# 130806_AriloRX_FINAL_PCB1.net
KiCad netlist of a schematic drawn in EAGLE
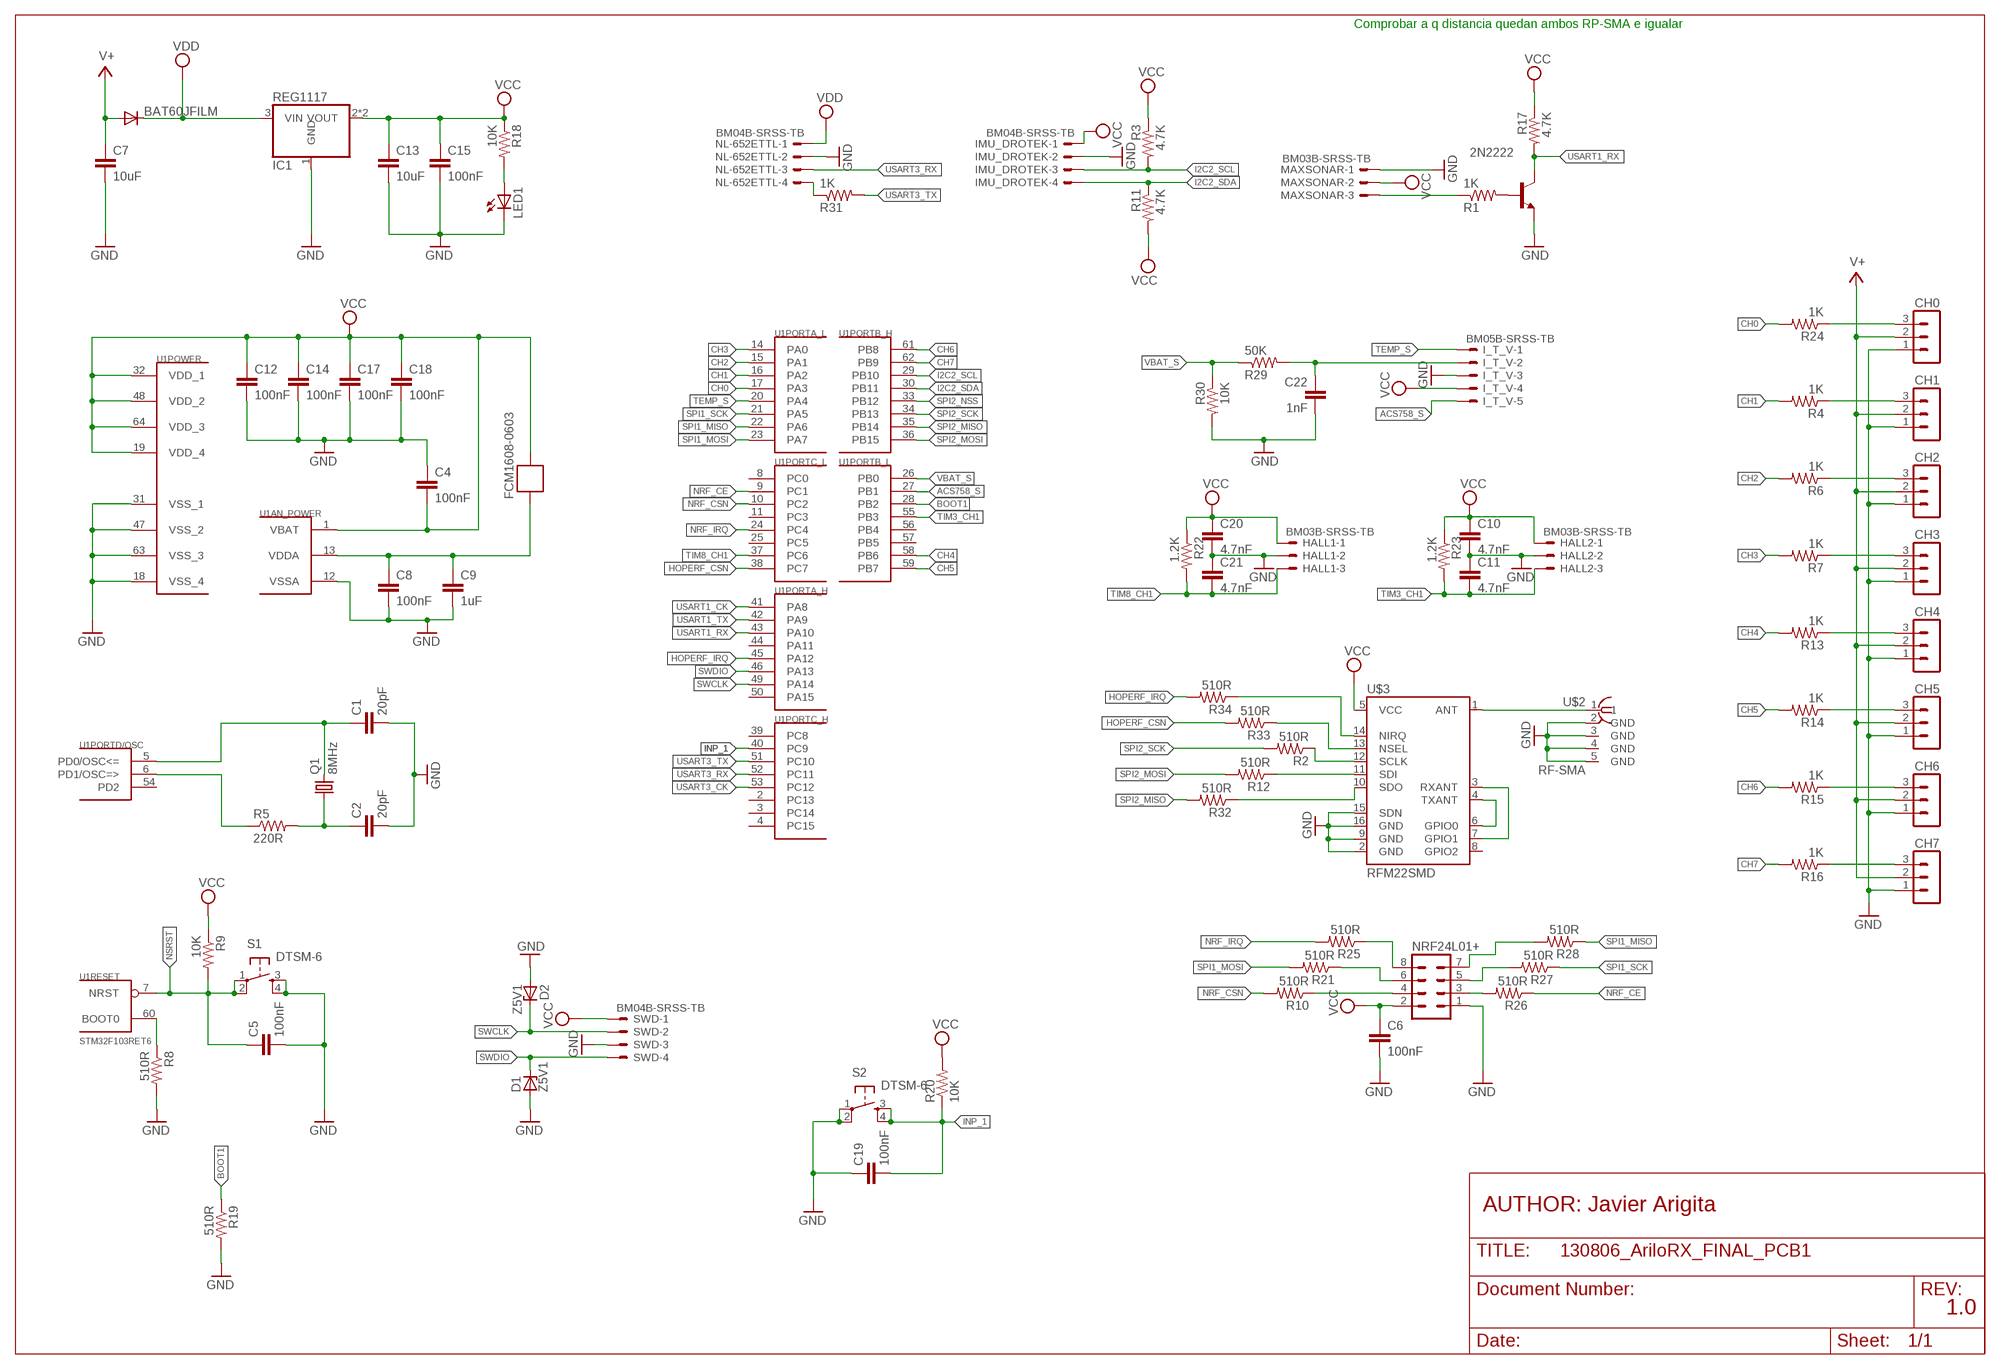
[diagram p0: schematic, sheet 1]

(export (version "E")
  (design (tool "Eeschema 10.0.6"))
  (components
    (comp (ref "2N2222")
      (value "MMBT2222ALT1-NPN-SOT23-BEC")
      (footprint "eagle-import:SOT23-BEC")
      (libsource (lib "eagle-import") (part "-NPN-SOT23-BECMMBT2222ALT1"))
    )
    (comp (ref "BAT60JFILM")
      (value "DIODE-SOD323-R")
      (footprint "eagle-import:SOD323-R")
      (libsource (lib "eagle-import") (part "DIODE-SOD323-R"))
    )
    (comp (ref "C1")
      (value "20pF")
      (footprint "eagle-import:C0805")
      (libsource (lib "eagle-import") (part "C-EUC0805"))
    )
    (comp (ref "C2")
      (value "20pF")
      (footprint "eagle-import:C0805")
      (libsource (lib "eagle-import") (part "C-EUC0805"))
    )
    (comp (ref "C4")
      (value "100nF")
      (footprint "eagle-import:C0805")
      (libsource (lib "eagle-import") (part "C-EUC0805"))
    )
    (comp (ref "C5")
      (value "100nF")
      (footprint "eagle-import:C0805")
      (libsource (lib "eagle-import") (part "C-EUC0805"))
    )
    (comp (ref "C6")
      (value "100nF")
      (footprint "eagle-import:C0805")
      (libsource (lib "eagle-import") (part "C-EUC0805"))
    )
    (comp (ref "C7")
      (value "10uF")
      (footprint "eagle-import:C3216")
      (libsource (lib "eagle-import") (part "resistor_C-EUC3216"))
    )
    (comp (ref "C8")
      (value "100nF")
      (footprint "eagle-import:C0805")
      (libsource (lib "eagle-import") (part "C-EUC0805"))
    )
    (comp (ref "C9")
      (value "1uF")
      (footprint "eagle-import:C3216")
      (libsource (lib "eagle-import") (part "resistor_C-EUC3216"))
    )
    (comp (ref "C10")
      (value "4.7nF")
      (footprint "eagle-import:C0805")
      (libsource (lib "eagle-import") (part "C-EUC0805"))
    )
    (comp (ref "C11")
      (value "4.7nF")
      (footprint "eagle-import:C0805")
      (libsource (lib "eagle-import") (part "C-EUC0805"))
    )
    (comp (ref "C12")
      (value "100nF")
      (footprint "eagle-import:C0805")
      (libsource (lib "eagle-import") (part "C-EUC0805"))
    )
    (comp (ref "C13")
      (value "10uF")
      (footprint "eagle-import:C3216")
      (libsource (lib "eagle-import") (part "resistor_C-EUC3216"))
    )
    (comp (ref "C14")
      (value "100nF")
      (footprint "eagle-import:C0805")
      (libsource (lib "eagle-import") (part "C-EUC0805"))
    )
    (comp (ref "C15")
      (value "100nF")
      (footprint "eagle-import:C0805")
      (libsource (lib "eagle-import") (part "C-EUC0805"))
    )
    (comp (ref "C17")
      (value "100nF")
      (footprint "eagle-import:C0805")
      (libsource (lib "eagle-import") (part "C-EUC0805"))
    )
    (comp (ref "C18")
      (value "100nF")
      (footprint "eagle-import:C0805")
      (libsource (lib "eagle-import") (part "C-EUC0805"))
    )
    (comp (ref "C19")
      (value "100nF")
      (footprint "eagle-import:C0805")
      (libsource (lib "eagle-import") (part "C-EUC0805"))
    )
    (comp (ref "C20")
      (value "4.7nF")
      (footprint "eagle-import:C0805")
      (libsource (lib "eagle-import") (part "C-EUC0805"))
    )
    (comp (ref "C21")
      (value "4.7nF")
      (footprint "eagle-import:C0805")
      (libsource (lib "eagle-import") (part "C-EUC0805"))
    )
    (comp (ref "C22")
      (value "1nF")
      (footprint "eagle-import:C0805")
      (libsource (lib "eagle-import") (part "C-EUC0805"))
    )
    (comp (ref "CH0")
      (value "MA03-1")
      (footprint "eagle-import:MA03-1")
      (libsource (lib "eagle-import") (part "MA03-1"))
    )
    (comp (ref "CH1")
      (value "MA03-1")
      (footprint "eagle-import:MA03-1")
      (libsource (lib "eagle-import") (part "MA03-1"))
    )
    (comp (ref "CH2")
      (value "MA03-1")
      (footprint "eagle-import:MA03-1")
      (libsource (lib "eagle-import") (part "MA03-1"))
    )
    (comp (ref "CH3")
      (value "MA03-1")
      (footprint "eagle-import:MA03-1")
      (libsource (lib "eagle-import") (part "MA03-1"))
    )
    (comp (ref "CH4")
      (value "MA03-1")
      (footprint "eagle-import:MA03-1")
      (libsource (lib "eagle-import") (part "MA03-1"))
    )
    (comp (ref "CH5")
      (value "MA03-1")
      (footprint "eagle-import:MA03-1")
      (libsource (lib "eagle-import") (part "MA03-1"))
    )
    (comp (ref "CH6")
      (value "MA03-1")
      (footprint "eagle-import:MA03-1")
      (libsource (lib "eagle-import") (part "MA03-1"))
    )
    (comp (ref "CH7")
      (value "MA03-1")
      (footprint "eagle-import:MA03-1")
      (libsource (lib "eagle-import") (part "MA03-1"))
    )
    (comp (ref "D1")
      (value "Z5V1")
      (footprint "eagle-import:SOD80C")
      (libsource (lib "eagle-import") (part "ZENER-DIODESOD80C"))
    )
    (comp (ref "D2")
      (value "Z5V1")
      (footprint "eagle-import:SOD80C")
      (libsource (lib "eagle-import") (part "ZENER-DIODESOD80C"))
    )
    (comp (ref "FCM1608-0603")
      (value "FERRITE-BEAD")
      (footprint "eagle-import:R0603")
      (libsource (lib "eagle-import") (part "FERRITE-BEAD"))
    )
    (comp (ref "HALL1")
      (value "BM03B-SRSS-TB")
      (footprint "eagle-import:BM03B-SRSS-TB")
      (libsource (lib "eagle-import") (part "?M03B-SRSS-TBB"))
    )
    (comp (ref "HALL2")
      (value "BM03B-SRSS-TB")
      (footprint "eagle-import:BM03B-SRSS-TB")
      (libsource (lib "eagle-import") (part "?M03B-SRSS-TBB"))
    )
    (comp (ref "IC1")
      (value "REG1117")
      (footprint "eagle-import:SOT223")
      (libsource (lib "eagle-import") (part "REG1117"))
    )
    (comp (ref "IMU_DROTEK")
      (value "BM04B-SRSS-TB")
      (footprint "eagle-import:BM04B-SRSS-TB")
      (libsource (lib "eagle-import") (part "?M04B-SRSS-TBB"))
    )
    (comp (ref "I_T_V")
      (value "BM05B-SRSS-TB")
      (footprint "eagle-import:BM05B-SRSS-TB")
      (libsource (lib "eagle-import") (part "?M05B-SRSS-TBB"))
    )
    (comp (ref "LED1")
      (value "LED0805")
      (footprint "eagle-import:CHIPLED_0805")
      (libsource (lib "eagle-import") (part "LED0805"))
    )
    (comp (ref "MAXSONAR")
      (value "BM03B-SRSS-TB")
      (footprint "eagle-import:BM03B-SRSS-TB")
      (libsource (lib "eagle-import") (part "?M03B-SRSS-TBB"))
    )
    (comp (ref "NL-652ETTL")
      (value "BM04B-SRSS-TB")
      (footprint "eagle-import:BM04B-SRSS-TB")
      (libsource (lib "eagle-import") (part "?M04B-SRSS-TBB"))
    )
    (comp (ref "NRF24L01+")
      (value "MA04-2")
      (footprint "eagle-import:MA04-2")
      (libsource (lib "eagle-import") (part "MA04-2"))
    )
    (comp (ref "Q1")
      (value "8MHz")
      (footprint "eagle-import:SM49")
      (libsource (lib "eagle-import") (part "CRYSTALSM49"))
    )
    (comp (ref "R1")
      (value "1K")
      (footprint "eagle-import:R0805")
      (libsource (lib "eagle-import") (part "RESISTOR0805"))
    )
    (comp (ref "R2")
      (value "510R")
      (footprint "eagle-import:R0805")
      (libsource (lib "eagle-import") (part "RESISTOR0805"))
    )
    (comp (ref "R3")
      (value "4.7K")
      (footprint "eagle-import:R0805")
      (libsource (lib "eagle-import") (part "RESISTOR0805"))
    )
    (comp (ref "R4")
      (value "1K")
      (footprint "eagle-import:R0805")
      (libsource (lib "eagle-import") (part "RESISTOR0805"))
    )
    (comp (ref "R5")
      (value "220R")
      (footprint "eagle-import:R0805")
      (libsource (lib "eagle-import") (part "RESISTOR0805"))
    )
    (comp (ref "R6")
      (value "1K")
      (footprint "eagle-import:R0805")
      (libsource (lib "eagle-import") (part "RESISTOR0805"))
    )
    (comp (ref "R7")
      (value "1K")
      (footprint "eagle-import:R0805")
      (libsource (lib "eagle-import") (part "RESISTOR0805"))
    )
    (comp (ref "R8")
      (value "510R")
      (footprint "eagle-import:R0805")
      (libsource (lib "eagle-import") (part "RESISTOR0805"))
    )
    (comp (ref "R9")
      (value "10K")
      (footprint "eagle-import:R0805")
      (libsource (lib "eagle-import") (part "RESISTOR0805"))
    )
    (comp (ref "R10")
      (value "510R")
      (footprint "eagle-import:R0805")
      (libsource (lib "eagle-import") (part "RESISTOR0805"))
    )
    (comp (ref "R11")
      (value "4.7K")
      (footprint "eagle-import:R0805")
      (libsource (lib "eagle-import") (part "RESISTOR0805"))
    )
    (comp (ref "R12")
      (value "510R")
      (footprint "eagle-import:R0805")
      (libsource (lib "eagle-import") (part "RESISTOR0805"))
    )
    (comp (ref "R13")
      (value "1K")
      (footprint "eagle-import:R0805")
      (libsource (lib "eagle-import") (part "RESISTOR0805"))
    )
    (comp (ref "R14")
      (value "1K")
      (footprint "eagle-import:R0805")
      (libsource (lib "eagle-import") (part "RESISTOR0805"))
    )
    (comp (ref "R15")
      (value "1K")
      (footprint "eagle-import:R0805")
      (libsource (lib "eagle-import") (part "RESISTOR0805"))
    )
    (comp (ref "R16")
      (value "1K")
      (footprint "eagle-import:R0805")
      (libsource (lib "eagle-import") (part "RESISTOR0805"))
    )
    (comp (ref "R17")
      (value "4.7K")
      (footprint "eagle-import:R0805")
      (libsource (lib "eagle-import") (part "RESISTOR0805"))
    )
    (comp (ref "R18")
      (value "10K")
      (footprint "eagle-import:R0805")
      (libsource (lib "eagle-import") (part "RESISTOR0805"))
    )
    (comp (ref "R19")
      (value "510R")
      (footprint "eagle-import:R0805")
      (libsource (lib "eagle-import") (part "RESISTOR0805"))
    )
    (comp (ref "R20")
      (value "10K")
      (footprint "eagle-import:R0805")
      (libsource (lib "eagle-import") (part "RESISTOR0805"))
    )
    (comp (ref "R21")
      (value "510R")
      (footprint "eagle-import:R0805")
      (libsource (lib "eagle-import") (part "RESISTOR0805"))
    )
    (comp (ref "R22")
      (value "1.2K")
      (footprint "eagle-import:R0805")
      (libsource (lib "eagle-import") (part "RESISTOR0805"))
    )
    (comp (ref "R23")
      (value "1.2K")
      (footprint "eagle-import:R0805")
      (libsource (lib "eagle-import") (part "RESISTOR0805"))
    )
    (comp (ref "R24")
      (value "1K")
      (footprint "eagle-import:R0805")
      (libsource (lib "eagle-import") (part "RESISTOR0805"))
    )
    (comp (ref "R25")
      (value "510R")
      (footprint "eagle-import:R0805")
      (libsource (lib "eagle-import") (part "RESISTOR0805"))
    )
    (comp (ref "R26")
      (value "510R")
      (footprint "eagle-import:R0805")
      (libsource (lib "eagle-import") (part "RESISTOR0805"))
    )
    (comp (ref "R27")
      (value "510R")
      (footprint "eagle-import:R0805")
      (libsource (lib "eagle-import") (part "RESISTOR0805"))
    )
    (comp (ref "R28")
      (value "510R")
      (footprint "eagle-import:R0805")
      (libsource (lib "eagle-import") (part "RESISTOR0805"))
    )
    (comp (ref "R29")
      (value "50K")
      (footprint "eagle-import:R0805")
      (libsource (lib "eagle-import") (part "RESISTOR0805"))
    )
    (comp (ref "R30")
      (value "10K")
      (footprint "eagle-import:R0805")
      (libsource (lib "eagle-import") (part "RESISTOR0805"))
    )
    (comp (ref "R31")
      (value "1K")
      (footprint "eagle-import:R0805")
      (libsource (lib "eagle-import") (part "RESISTOR0805"))
    )
    (comp (ref "R32")
      (value "510R")
      (footprint "eagle-import:R0805")
      (libsource (lib "eagle-import") (part "RESISTOR0805"))
    )
    (comp (ref "R33")
      (value "510R")
      (footprint "eagle-import:R0805")
      (libsource (lib "eagle-import") (part "RESISTOR0805"))
    )
    (comp (ref "R34")
      (value "510R")
      (footprint "eagle-import:R0805")
      (libsource (lib "eagle-import") (part "RESISTOR0805"))
    )
    (comp (ref "S1")
      (value "DTSM-6")
      (footprint "eagle-import:DTSM-6")
      (libsource (lib "eagle-import") (part "DTSM-6"))
    )
    (comp (ref "S2")
      (value "DTSM-6")
      (footprint "eagle-import:DTSM-6")
      (libsource (lib "eagle-import") (part "DTSM-6"))
    )
    (comp (ref "SWD")
      (value "BM04B-SRSS-TB")
      (footprint "eagle-import:BM04B-SRSS-TB")
      (libsource (lib "eagle-import") (part "?M04B-SRSS-TBB"))
    )
    (comp (ref "U$2")
      (value "RF-SMA")
      (footprint "eagle-import:BU-SMA-H")
      (libsource (lib "eagle-import") (part "RF-SMA"))
    )
    (comp (ref "U$3")
      (value "RFM22SMD")
      (footprint "eagle-import:RFM22-XXX-S2")
      (libsource (lib "eagle-import") (part "RFM22SMD"))
    )
    (comp (ref "U1")
      (value "STM32F103RET6")
      (footprint "eagle-import:TQFP64")
      (libsource (lib "eagle-import") (part "STM32F10XRXT6"))
    )
  )
  (nets
    (net (code "1") (name "ACS758_S") (class "Default")
      (node (ref "I_T_V") (pin "5") (pinfunction "S_5") (pintype "passive"))
      (node (ref "U1") (pin "27") (pinfunction "PB1_27") (pintype "bidirectional"))
    )
    (net (code "2") (name "BOOT1") (class "Default")
      (node (ref "R19") (pin "1") (pinfunction "1_1") (pintype "passive"))
      (node (ref "U1") (pin "28") (pinfunction "PB2_28") (pintype "bidirectional"))
    )
    (net (code "3") (name "CH0") (class "Default")
      (node (ref "R24") (pin "2") (pinfunction "2_2") (pintype "passive"))
      (node (ref "U1") (pin "17") (pinfunction "PA3_17") (pintype "bidirectional"))
    )
    (net (code "4") (name "CH1") (class "Default")
      (node (ref "R4") (pin "2") (pinfunction "2_2") (pintype "passive"))
      (node (ref "U1") (pin "16") (pinfunction "PA2_16") (pintype "bidirectional"))
    )
    (net (code "5") (name "CH2") (class "Default")
      (node (ref "R6") (pin "2") (pinfunction "2_2") (pintype "passive"))
      (node (ref "U1") (pin "15") (pinfunction "PA1_15") (pintype "bidirectional"))
    )
    (net (code "6") (name "CH3") (class "Default")
      (node (ref "R7") (pin "2") (pinfunction "2_2") (pintype "passive"))
      (node (ref "U1") (pin "14") (pinfunction "PA0_14") (pintype "bidirectional"))
    )
    (net (code "7") (name "CH4") (class "Default")
      (node (ref "R13") (pin "2") (pinfunction "2_2") (pintype "passive"))
      (node (ref "U1") (pin "58") (pinfunction "PB6_58") (pintype "bidirectional"))
    )
    (net (code "8") (name "CH5") (class "Default")
      (node (ref "R14") (pin "2") (pinfunction "2_2") (pintype "passive"))
      (node (ref "U1") (pin "59") (pinfunction "PB7_59") (pintype "bidirectional"))
    )
    (net (code "9") (name "CH6") (class "Default")
      (node (ref "R15") (pin "2") (pinfunction "2_2") (pintype "passive"))
      (node (ref "U1") (pin "61") (pinfunction "PB8_61") (pintype "bidirectional"))
    )
    (net (code "10") (name "CH7") (class "Default")
      (node (ref "R16") (pin "2") (pinfunction "2_2") (pintype "passive"))
      (node (ref "U1") (pin "62") (pinfunction "PB9_62") (pintype "bidirectional"))
    )
    (net (code "11") (name "GND") (class "Default")
      (node (ref "2N2222") (pin "E") (pinfunction "E_E") (pintype "passive"))
      (node (ref "C1") (pin "2") (pinfunction "2_2") (pintype "passive"))
      (node (ref "C10") (pin "2") (pinfunction "2_2") (pintype "passive"))
      (node (ref "C11") (pin "1") (pinfunction "1_1") (pintype "passive"))
      (node (ref "C12") (pin "2") (pinfunction "2_2") (pintype "passive"))
      (node (ref "C13") (pin "2") (pinfunction "2_2") (pintype "passive"))
      (node (ref "C14") (pin "2") (pinfunction "2_2") (pintype "passive"))
      (node (ref "C15") (pin "2") (pinfunction "2_2") (pintype "passive"))
      (node (ref "C17") (pin "2") (pinfunction "2_2") (pintype "passive"))
      (node (ref "C18") (pin "2") (pinfunction "2_2") (pintype "passive"))
      (node (ref "C19") (pin "1") (pinfunction "1_1") (pintype "passive"))
      (node (ref "C2") (pin "2") (pinfunction "2_2") (pintype "passive"))
      (node (ref "C20") (pin "2") (pinfunction "2_2") (pintype "passive"))
      (node (ref "C21") (pin "1") (pinfunction "1_1") (pintype "passive"))
      (node (ref "C22") (pin "2") (pinfunction "2_2") (pintype "passive"))
      (node (ref "C4") (pin "1") (pinfunction "1_1") (pintype "passive"))
      (node (ref "C5") (pin "2") (pinfunction "2_2") (pintype "passive"))
      (node (ref "C6") (pin "2") (pinfunction "2_2") (pintype "passive"))
      (node (ref "C7") (pin "2") (pinfunction "2_2") (pintype "passive"))
      (node (ref "C8") (pin "2") (pinfunction "2_2") (pintype "passive"))
      (node (ref "C9") (pin "2") (pinfunction "2_2") (pintype "passive"))
      (node (ref "CH0") (pin "1") (pinfunction "1_1") (pintype "passive"))
      (node (ref "CH1") (pin "1") (pinfunction "1_1") (pintype "passive"))
      (node (ref "CH2") (pin "1") (pinfunction "1_1") (pintype "passive"))
      (node (ref "CH3") (pin "1") (pinfunction "1_1") (pintype "passive"))
      (node (ref "CH4") (pin "1") (pinfunction "1_1") (pintype "passive"))
      (node (ref "CH5") (pin "1") (pinfunction "1_1") (pintype "passive"))
      (node (ref "CH6") (pin "1") (pinfunction "1_1") (pintype "passive"))
      (node (ref "CH7") (pin "1") (pinfunction "1_1") (pintype "passive"))
      (node (ref "D1") (pin "A") (pinfunction "A_A") (pintype "passive"))
      (node (ref "D2") (pin "A") (pinfunction "A_A") (pintype "passive"))
      (node (ref "HALL1") (pin "2") (pinfunction "S_2") (pintype "passive"))
      (node (ref "HALL2") (pin "2") (pinfunction "S_2") (pintype "passive"))
      (node (ref "IC1") (pin "1") (pinfunction "GND_1") (pintype "power_in"))
      (node (ref "IMU_DROTEK") (pin "2") (pinfunction "S_2") (pintype "passive"))
      (node (ref "I_T_V") (pin "3") (pinfunction "S_3") (pintype "passive"))
      (node (ref "LED1") (pin "C") (pinfunction "C_C") (pintype "passive"))
      (node (ref "MAXSONAR") (pin "1") (pinfunction "S_1") (pintype "passive"))
      (node (ref "NL-652ETTL") (pin "2") (pinfunction "S_2") (pintype "passive"))
      (node (ref "NRF24L01+") (pin "1") (pinfunction "1_1") (pintype "passive"))
      (node (ref "R19") (pin "2") (pinfunction "2_2") (pintype "passive"))
      (node (ref "R30") (pin "2") (pinfunction "2_2") (pintype "passive"))
      (node (ref "R8") (pin "2") (pinfunction "2_2") (pintype "passive"))
      (node (ref "S1") (pin "3") (pinfunction "3_3") (pintype "passive"))
      (node (ref "S1") (pin "4") (pinfunction "4_4") (pintype "passive"))
      (node (ref "S2") (pin "1") (pinfunction "1_1") (pintype "passive"))
      (node (ref "S2") (pin "2") (pinfunction "2_2") (pintype "passive"))
      (node (ref "SWD") (pin "3") (pinfunction "S_3") (pintype "passive"))
      (node (ref "U$2") (pin "2") (pinfunction "GND_2") (pintype "power_in"))
      (node (ref "U$2") (pin "3") (pinfunction "GND_3") (pintype "bidirectional"))
      (node (ref "U$2") (pin "4") (pinfunction "GND_4") (pintype "bidirectional"))
      (node (ref "U$2") (pin "5") (pinfunction "GND_5") (pintype "bidirectional"))
      (node (ref "U$3") (pin "15") (pinfunction "SDN_15") (pintype "input"))
      (node (ref "U$3") (pin "16") (pinfunction "GND_16") (pintype "power_in"))
      (node (ref "U$3") (pin "2") (pinfunction "GND_2") (pintype "power_in"))
      (node (ref "U$3") (pin "9") (pinfunction "GND_9") (pintype "power_in"))
      (node (ref "U1") (pin "12") (pinfunction "VSSA_12") (pintype "power_in"))
      (node (ref "U1") (pin "18") (pinfunction "VSS_4_18") (pintype "power_in"))
      (node (ref "U1") (pin "31") (pinfunction "VSS_1_31") (pintype "power_in"))
      (node (ref "U1") (pin "47") (pinfunction "VSS_2_47") (pintype "power_in"))
      (node (ref "U1") (pin "63") (pinfunction "VSS_3_63") (pintype "power_in"))
    )
    (net (code "12") (name "HOPERF_CSN") (class "Default")
      (node (ref "R33") (pin "2") (pinfunction "2_2") (pintype "passive"))
      (node (ref "U1") (pin "38") (pinfunction "PC7_38") (pintype "bidirectional"))
    )
    (net (code "13") (name "HOPERF_IRQ") (class "Default")
      (node (ref "R34") (pin "2") (pinfunction "2_2") (pintype "passive"))
      (node (ref "U1") (pin "45") (pinfunction "PA12_45") (pintype "bidirectional"))
    )
    (net (code "14") (name "I2C2_SCL") (class "Default")
      (node (ref "IMU_DROTEK") (pin "3") (pinfunction "S_3") (pintype "passive"))
      (node (ref "R3") (pin "2") (pinfunction "2_2") (pintype "passive"))
      (node (ref "U1") (pin "29") (pinfunction "PB10_29") (pintype "bidirectional"))
    )
    (net (code "15") (name "I2C2_SDA") (class "Default")
      (node (ref "IMU_DROTEK") (pin "4") (pinfunction "S_4") (pintype "passive"))
      (node (ref "R11") (pin "1") (pinfunction "1_1") (pintype "passive"))
      (node (ref "U1") (pin "30") (pinfunction "PB11_30") (pintype "bidirectional"))
    )
    (net (code "16") (name "INP_1") (class "Default")
      (node (ref "C19") (pin "2") (pinfunction "2_2") (pintype "passive"))
      (node (ref "R20") (pin "1") (pinfunction "1_1") (pintype "passive"))
      (node (ref "S2") (pin "3") (pinfunction "3_3") (pintype "passive"))
      (node (ref "S2") (pin "4") (pinfunction "4_4") (pintype "passive"))
      (node (ref "U1") (pin "40") (pinfunction "PC9_40") (pintype "bidirectional"))
    )
    (net (code "17") (name "NRF_CE") (class "Default")
      (node (ref "R26") (pin "1") (pinfunction "1_1") (pintype "passive"))
      (node (ref "U1") (pin "9") (pinfunction "PC1_9") (pintype "bidirectional"))
    )
    (net (code "18") (name "NRF_CSN") (class "Default")
      (node (ref "R10") (pin "2") (pinfunction "2_2") (pintype "passive"))
      (node (ref "U1") (pin "10") (pinfunction "PC2_10") (pintype "bidirectional"))
    )
    (net (code "19") (name "NRF_IRQ") (class "Default")
      (node (ref "R25") (pin "2") (pinfunction "2_2") (pintype "passive"))
      (node (ref "U1") (pin "24") (pinfunction "PC4_24") (pintype "bidirectional"))
    )
    (net (code "20") (name "NSRST") (class "Default")
      (node (ref "C5") (pin "1") (pinfunction "1_1") (pintype "passive"))
      (node (ref "R9") (pin "2") (pinfunction "2_2") (pintype "passive"))
      (node (ref "S1") (pin "1") (pinfunction "1_1") (pintype "passive"))
      (node (ref "S1") (pin "2") (pinfunction "2_2") (pintype "passive"))
      (node (ref "U1") (pin "7") (pinfunction "NRST_7") (pintype "input"))
    )
    (net (code "21") (name "Net-(2N2222-PadB)") (class "Default")
      (node (ref "2N2222") (pin "B") (pinfunction "B_B") (pintype "passive"))
      (node (ref "R1") (pin "2") (pinfunction "2_2") (pintype "passive"))
    )
    (net (code "22") (name "Net-(C2-Pad1)") (class "Default")
      (node (ref "C2") (pin "1") (pinfunction "1_1") (pintype "passive"))
      (node (ref "Q1") (pin "1") (pinfunction "1_1") (pintype "passive"))
      (node (ref "R5") (pin "2") (pinfunction "2_2") (pintype "passive"))
    )
    (net (code "23") (name "Net-(CH0-Pad3)") (class "Default")
      (node (ref "CH0") (pin "3") (pinfunction "3_3") (pintype "passive"))
      (node (ref "R24") (pin "1") (pinfunction "1_1") (pintype "passive"))
    )
    (net (code "24") (name "Net-(CH1-Pad3)") (class "Default")
      (node (ref "CH1") (pin "3") (pinfunction "3_3") (pintype "passive"))
      (node (ref "R4") (pin "1") (pinfunction "1_1") (pintype "passive"))
    )
    (net (code "25") (name "Net-(CH2-Pad3)") (class "Default")
      (node (ref "CH2") (pin "3") (pinfunction "3_3") (pintype "passive"))
      (node (ref "R6") (pin "1") (pinfunction "1_1") (pintype "passive"))
    )
    (net (code "26") (name "Net-(CH3-Pad3)") (class "Default")
      (node (ref "CH3") (pin "3") (pinfunction "3_3") (pintype "passive"))
      (node (ref "R7") (pin "1") (pinfunction "1_1") (pintype "passive"))
    )
    (net (code "27") (name "Net-(CH4-Pad3)") (class "Default")
      (node (ref "CH4") (pin "3") (pinfunction "3_3") (pintype "passive"))
      (node (ref "R13") (pin "1") (pinfunction "1_1") (pintype "passive"))
    )
    (net (code "28") (name "Net-(CH5-Pad3)") (class "Default")
      (node (ref "CH5") (pin "3") (pinfunction "3_3") (pintype "passive"))
      (node (ref "R14") (pin "1") (pinfunction "1_1") (pintype "passive"))
    )
    (net (code "29") (name "Net-(CH6-Pad3)") (class "Default")
      (node (ref "CH6") (pin "3") (pinfunction "3_3") (pintype "passive"))
      (node (ref "R15") (pin "1") (pinfunction "1_1") (pintype "passive"))
    )
    (net (code "30") (name "Net-(CH7-Pad3)") (class "Default")
      (node (ref "CH7") (pin "3") (pinfunction "3_3") (pintype "passive"))
      (node (ref "R16") (pin "1") (pinfunction "1_1") (pintype "passive"))
    )
    (net (code "31") (name "Net-(FCM1608-0603-P$2)") (class "Default")
      (node (ref "C8") (pin "1") (pinfunction "1_1") (pintype "passive"))
      (node (ref "C9") (pin "1") (pinfunction "1_1") (pintype "passive"))
      (node (ref "FCM1608-0603") (pin "2") (pinfunction "P$2_2") (pintype "bidirectional"))
      (node (ref "U1") (pin "13") (pinfunction "VDDA_13") (pintype "power_in"))
    )
    (net (code "32") (name "Net-(I_T_VB-S)") (class "Default")
      (node (ref "C22") (pin "1") (pinfunction "1_1") (pintype "passive"))
      (node (ref "I_T_V") (pin "2") (pinfunction "S_2") (pintype "passive"))
      (node (ref "R29") (pin "2") (pinfunction "2_2") (pintype "passive"))
    )
    (net (code "33") (name "Net-(LED1-PadA)") (class "Default")
      (node (ref "LED1") (pin "A") (pinfunction "A_A") (pintype "passive"))
      (node (ref "R18") (pin "2") (pinfunction "2_2") (pintype "passive"))
    )
    (net (code "34") (name "Net-(MAXSONARC-S)") (class "Default")
      (node (ref "MAXSONAR") (pin "3") (pinfunction "S_3") (pintype "passive"))
      (node (ref "R1") (pin "1") (pinfunction "1_1") (pintype "passive"))
    )
    (net (code "35") (name "Net-(NL-652ETTLD-S)") (class "Default")
      (node (ref "NL-652ETTL") (pin "4") (pinfunction "S_4") (pintype "passive"))
      (node (ref "R31") (pin "1") (pinfunction "1_1") (pintype "passive"))
    )
    (net (code "36") (name "Net-(NRF24L01+-Pad3)") (class "Default")
      (node (ref "NRF24L01+") (pin "3") (pinfunction "3_3") (pintype "passive"))
      (node (ref "R26") (pin "2") (pinfunction "2_2") (pintype "passive"))
    )
    (net (code "37") (name "Net-(NRF24L01+-Pad4)") (class "Default")
      (node (ref "NRF24L01+") (pin "4") (pinfunction "4_4") (pintype "passive"))
      (node (ref "R10") (pin "1") (pinfunction "1_1") (pintype "passive"))
    )
    (net (code "38") (name "Net-(NRF24L01+-Pad5)") (class "Default")
      (node (ref "NRF24L01+") (pin "5") (pinfunction "5_5") (pintype "passive"))
      (node (ref "R27") (pin "2") (pinfunction "2_2") (pintype "passive"))
    )
    (net (code "39") (name "Net-(NRF24L01+-Pad6)") (class "Default")
      (node (ref "NRF24L01+") (pin "6") (pinfunction "6_6") (pintype "passive"))
      (node (ref "R21") (pin "1") (pinfunction "1_1") (pintype "passive"))
    )
    (net (code "40") (name "Net-(NRF24L01+-Pad7)") (class "Default")
      (node (ref "NRF24L01+") (pin "7") (pinfunction "7_7") (pintype "passive"))
      (node (ref "R28") (pin "2") (pinfunction "2_2") (pintype "passive"))
    )
    (net (code "41") (name "Net-(NRF24L01+-Pad8)") (class "Default")
      (node (ref "NRF24L01+") (pin "8") (pinfunction "8_8") (pintype "passive"))
      (node (ref "R25") (pin "1") (pinfunction "1_1") (pintype "passive"))
    )
    (net (code "42") (name "Net-(U$3-ANT)") (class "Default")
      (node (ref "U$2") (pin "1") (pinfunction "1_1") (pintype "passive"))
      (node (ref "U$3") (pin "1") (pinfunction "ANT_1") (pintype "bidirectional"))
    )
    (net (code "43") (name "Net-(U$3-GPIO0)") (class "Default")
      (node (ref "U$3") (pin "4") (pinfunction "TXANT_4") (pintype "input"))
      (node (ref "U$3") (pin "6") (pinfunction "GPIO0_6") (pintype "bidirectional"))
    )
    (net (code "44") (name "Net-(U$3-GPIO1)") (class "Default")
      (node (ref "U$3") (pin "3") (pinfunction "RXANT_3") (pintype "input"))
      (node (ref "U$3") (pin "7") (pinfunction "GPIO1_7") (pintype "bidirectional"))
    )
    (net (code "45") (name "Net-(U$3-NIRQ)") (class "Default")
      (node (ref "R34") (pin "1") (pinfunction "1_1") (pintype "passive"))
      (node (ref "U$3") (pin "14") (pinfunction "NIRQ_14") (pintype "output"))
    )
    (net (code "46") (name "Net-(U$3-NSEL)") (class "Default")
      (node (ref "R33") (pin "1") (pinfunction "1_1") (pintype "passive"))
      (node (ref "U$3") (pin "13") (pinfunction "NSEL_13") (pintype "input"))
    )
    (net (code "47") (name "Net-(U$3-SCLK)") (class "Default")
      (node (ref "R2") (pin "1") (pinfunction "1_1") (pintype "passive"))
      (node (ref "U$3") (pin "12") (pinfunction "SCLK_12") (pintype "input"))
    )
    (net (code "48") (name "Net-(U$3-SDI)") (class "Default")
      (node (ref "R12") (pin "1") (pinfunction "1_1") (pintype "passive"))
      (node (ref "U$3") (pin "11") (pinfunction "SDI_11") (pintype "input"))
    )
    (net (code "49") (name "Net-(U$3-SDO)") (class "Default")
      (node (ref "R32") (pin "1") (pinfunction "1_1") (pintype "passive"))
      (node (ref "U$3") (pin "10") (pinfunction "SDO_10") (pintype "output"))
    )
    (net (code "50") (name "Net-(U1H-PD0{slash}OSC<=)") (class "Default")
      (node (ref "C1") (pin "1") (pinfunction "1_1") (pintype "passive"))
      (node (ref "Q1") (pin "2") (pinfunction "2_2") (pintype "passive"))
      (node (ref "U1") (pin "5") (pinfunction "PD0/OSC<=_5") (pintype "bidirectional"))
    )
    (net (code "51") (name "Net-(U1H-PD1{slash}OSC=>)") (class "Default")
      (node (ref "R5") (pin "1") (pinfunction "1_1") (pintype "passive"))
      (node (ref "U1") (pin "6") (pinfunction "PD1/OSC=>_6") (pintype "bidirectional"))
    )
    (net (code "52") (name "Net-(U1J-BOOT0)") (class "Default")
      (node (ref "R8") (pin "1") (pinfunction "1_1") (pintype "passive"))
      (node (ref "U1") (pin "60") (pinfunction "BOOT0_60") (pintype "input"))
    )
    (net (code "53") (name "SPI1_MISO") (class "Default")
      (node (ref "R28") (pin "1") (pinfunction "1_1") (pintype "passive"))
      (node (ref "U1") (pin "22") (pinfunction "PA6_22") (pintype "bidirectional"))
    )
    (net (code "54") (name "SPI1_MOSI") (class "Default")
      (node (ref "R21") (pin "2") (pinfunction "2_2") (pintype "passive"))
      (node (ref "U1") (pin "23") (pinfunction "PA7_23") (pintype "bidirectional"))
    )
    (net (code "55") (name "SPI1_SCK") (class "Default")
      (node (ref "R27") (pin "1") (pinfunction "1_1") (pintype "passive"))
      (node (ref "U1") (pin "21") (pinfunction "PA5_21") (pintype "bidirectional"))
    )
    (net (code "56") (name "SPI2_MISO") (class "Default")
      (node (ref "R32") (pin "2") (pinfunction "2_2") (pintype "passive"))
      (node (ref "U1") (pin "35") (pinfunction "PB14_35") (pintype "bidirectional"))
    )
    (net (code "57") (name "SPI2_MOSI") (class "Default")
      (node (ref "R12") (pin "2") (pinfunction "2_2") (pintype "passive"))
      (node (ref "U1") (pin "36") (pinfunction "PB15_36") (pintype "bidirectional"))
    )
    (net (code "58") (name "SPI2_NSS") (class "Default")
      (node (ref "U1") (pin "33") (pinfunction "PB12_33") (pintype "bidirectional"))
    )
    (net (code "59") (name "SPI2_SCK") (class "Default")
      (node (ref "R2") (pin "2") (pinfunction "2_2") (pintype "passive"))
      (node (ref "U1") (pin "34") (pinfunction "PB13_34") (pintype "bidirectional"))
    )
    (net (code "60") (name "SWCLK") (class "Default")
      (node (ref "D2") (pin "C") (pinfunction "C_C") (pintype "passive"))
      (node (ref "SWD") (pin "2") (pinfunction "S_2") (pintype "passive"))
      (node (ref "U1") (pin "49") (pinfunction "PA14_49") (pintype "bidirectional"))
    )
    (net (code "61") (name "SWDIO") (class "Default")
      (node (ref "D1") (pin "C") (pinfunction "C_C") (pintype "passive"))
      (node (ref "SWD") (pin "4") (pinfunction "S_4") (pintype "passive"))
      (node (ref "U1") (pin "46") (pinfunction "PA13_46") (pintype "bidirectional"))
    )
    (net (code "62") (name "TEMP_S") (class "Default")
      (node (ref "I_T_V") (pin "1") (pinfunction "S_1") (pintype "passive"))
      (node (ref "U1") (pin "20") (pinfunction "PA4_20") (pintype "bidirectional"))
    )
    (net (code "63") (name "TIM3_CH1") (class "Default")
      (node (ref "C11") (pin "2") (pinfunction "2_2") (pintype "passive"))
      (node (ref "HALL2") (pin "3") (pinfunction "S_3") (pintype "passive"))
      (node (ref "R23") (pin "2") (pinfunction "2_2") (pintype "passive"))
      (node (ref "U1") (pin "55") (pinfunction "PB3_55") (pintype "bidirectional"))
    )
    (net (code "64") (name "TIM8_CH1") (class "Default")
      (node (ref "C21") (pin "2") (pinfunction "2_2") (pintype "passive"))
      (node (ref "HALL1") (pin "3") (pinfunction "S_3") (pintype "passive"))
      (node (ref "R22") (pin "2") (pinfunction "2_2") (pintype "passive"))
      (node (ref "U1") (pin "37") (pinfunction "PC6_37") (pintype "bidirectional"))
    )
    (net (code "65") (name "USART1_CK") (class "Default")
      (node (ref "U1") (pin "41") (pinfunction "PA8_41") (pintype "bidirectional"))
    )
    (net (code "66") (name "USART1_RX") (class "Default")
      (node (ref "2N2222") (pin "C") (pinfunction "C_C") (pintype "passive"))
      (node (ref "R17") (pin "2") (pinfunction "2_2") (pintype "passive"))
      (node (ref "U1") (pin "43") (pinfunction "PA10_43") (pintype "bidirectional"))
    )
    (net (code "67") (name "USART1_TX") (class "Default")
      (node (ref "U1") (pin "42") (pinfunction "PA9_42") (pintype "bidirectional"))
    )
    (net (code "68") (name "USART3_CK") (class "Default")
      (node (ref "U1") (pin "53") (pinfunction "PC12_53") (pintype "bidirectional"))
    )
    (net (code "69") (name "USART3_RX") (class "Default")
      (node (ref "NL-652ETTL") (pin "3") (pinfunction "S_3") (pintype "passive"))
      (node (ref "U1") (pin "52") (pinfunction "PC11_52") (pintype "bidirectional"))
    )
    (net (code "70") (name "USART3_TX") (class "Default")
      (node (ref "R31") (pin "2") (pinfunction "2_2") (pintype "passive"))
      (node (ref "U1") (pin "51") (pinfunction "PC10_51") (pintype "bidirectional"))
    )
    (net (code "71") (name "V+") (class "Default")
      (node (ref "BAT60JFILM") (pin "A") (pinfunction "A_A") (pintype "passive"))
      (node (ref "C7") (pin "1") (pinfunction "1_1") (pintype "passive"))
      (node (ref "CH0") (pin "2") (pinfunction "2_2") (pintype "passive"))
      (node (ref "CH1") (pin "2") (pinfunction "2_2") (pintype "passive"))
      (node (ref "CH2") (pin "2") (pinfunction "2_2") (pintype "passive"))
      (node (ref "CH3") (pin "2") (pinfunction "2_2") (pintype "passive"))
      (node (ref "CH4") (pin "2") (pinfunction "2_2") (pintype "passive"))
      (node (ref "CH5") (pin "2") (pinfunction "2_2") (pintype "passive"))
      (node (ref "CH6") (pin "2") (pinfunction "2_2") (pintype "passive"))
      (node (ref "CH7") (pin "2") (pinfunction "2_2") (pintype "passive"))
    )
    (net (code "72") (name "VBAT_S") (class "Default")
      (node (ref "R29") (pin "1") (pinfunction "1_1") (pintype "passive"))
      (node (ref "R30") (pin "1") (pinfunction "1_1") (pintype "passive"))
      (node (ref "U1") (pin "26") (pinfunction "PB0_26") (pintype "bidirectional"))
    )
    (net (code "73") (name "VCC") (class "Default")
      (node (ref "C10") (pin "1") (pinfunction "1_1") (pintype "passive"))
      (node (ref "C12") (pin "1") (pinfunction "1_1") (pintype "passive"))
      (node (ref "C13") (pin "1") (pinfunction "1_1") (pintype "passive"))
      (node (ref "C14") (pin "1") (pinfunction "1_1") (pintype "passive"))
      (node (ref "C15") (pin "1") (pinfunction "1_1") (pintype "passive"))
      (node (ref "C17") (pin "1") (pinfunction "1_1") (pintype "passive"))
      (node (ref "C18") (pin "1") (pinfunction "1_1") (pintype "passive"))
      (node (ref "C20") (pin "1") (pinfunction "1_1") (pintype "passive"))
      (node (ref "C4") (pin "2") (pinfunction "2_2") (pintype "passive"))
      (node (ref "C6") (pin "1") (pinfunction "1_1") (pintype "passive"))
      (node (ref "FCM1608-0603") (pin "1") (pinfunction "P$1_1") (pintype "bidirectional"))
      (node (ref "HALL1") (pin "1") (pinfunction "S_1") (pintype "passive"))
      (node (ref "HALL2") (pin "1") (pinfunction "S_1") (pintype "passive"))
      (node (ref "IC1") (pin "2") (pinfunction "VOUT_2") (pintype "power_in"))
      (node (ref "IC1") (pin "4") (pinfunction "VOUT_4") (pintype "power_in"))
      (node (ref "IMU_DROTEK") (pin "1") (pinfunction "S_1") (pintype "passive"))
      (node (ref "I_T_V") (pin "4") (pinfunction "S_4") (pintype "passive"))
      (node (ref "MAXSONAR") (pin "2") (pinfunction "S_2") (pintype "passive"))
      (node (ref "NRF24L01+") (pin "2") (pinfunction "2_2") (pintype "passive"))
      (node (ref "R11") (pin "2") (pinfunction "2_2") (pintype "passive"))
      (node (ref "R17") (pin "1") (pinfunction "1_1") (pintype "passive"))
      (node (ref "R18") (pin "1") (pinfunction "1_1") (pintype "passive"))
      (node (ref "R20") (pin "2") (pinfunction "2_2") (pintype "passive"))
      (node (ref "R22") (pin "1") (pinfunction "1_1") (pintype "passive"))
      (node (ref "R23") (pin "1") (pinfunction "1_1") (pintype "passive"))
      (node (ref "R3") (pin "1") (pinfunction "1_1") (pintype "passive"))
      (node (ref "R9") (pin "1") (pinfunction "1_1") (pintype "passive"))
      (node (ref "SWD") (pin "1") (pinfunction "S_1") (pintype "passive"))
      (node (ref "U$3") (pin "5") (pinfunction "VCC_5") (pintype "bidirectional"))
      (node (ref "U1") (pin "1") (pinfunction "VBAT_1") (pintype "power_in"))
      (node (ref "U1") (pin "19") (pinfunction "VDD_4_19") (pintype "power_in"))
      (node (ref "U1") (pin "32") (pinfunction "VDD_1_32") (pintype "power_in"))
      (node (ref "U1") (pin "48") (pinfunction "VDD_2_48") (pintype "power_in"))
      (node (ref "U1") (pin "64") (pinfunction "VDD_3_64") (pintype "power_in"))
    )
    (net (code "74") (name "VDD") (class "Default")
      (node (ref "BAT60JFILM") (pin "C") (pinfunction "C_C") (pintype "passive"))
      (node (ref "IC1") (pin "3") (pinfunction "VIN_3") (pintype "input"))
      (node (ref "NL-652ETTL") (pin "1") (pinfunction "S_1") (pintype "passive"))
    )
    (net (code "75") (name "unconnected-(U$3-GPIO2-Pad8)") (class "Default")
      (node (ref "U$3") (pin "8") (pinfunction "GPIO2_8") (pintype "bidirectional"))
    )
    (net (code "76") (name "unconnected-(U1B-PA11-Pad44)") (class "Default")
      (node (ref "U1") (pin "44") (pinfunction "PA11_44") (pintype "bidirectional"))
    )
    (net (code "77") (name "unconnected-(U1B-PA15-Pad50)") (class "Default")
      (node (ref "U1") (pin "50") (pinfunction "PA15_50") (pintype "bidirectional"))
    )
    (net (code "78") (name "unconnected-(U1E-PB4-Pad56)") (class "Default")
      (node (ref "U1") (pin "56") (pinfunction "PB4_56") (pintype "bidirectional"))
    )
    (net (code "79") (name "unconnected-(U1E-PB5-Pad57)") (class "Default")
      (node (ref "U1") (pin "57") (pinfunction "PB5_57") (pintype "bidirectional"))
    )
    (net (code "80") (name "unconnected-(U1F-PC8-Pad39)") (class "Default")
      (node (ref "U1") (pin "39") (pinfunction "PC8_39") (pintype "bidirectional"))
    )
    (net (code "81") (name "unconnected-(U1F-PC13-Pad2)") (class "Default")
      (node (ref "U1") (pin "2") (pinfunction "PC13_2") (pintype "bidirectional"))
    )
    (net (code "82") (name "unconnected-(U1F-PC14-Pad3)") (class "Default")
      (node (ref "U1") (pin "3") (pinfunction "PC14_3") (pintype "bidirectional"))
    )
    (net (code "83") (name "unconnected-(U1F-PC15-Pad4)") (class "Default")
      (node (ref "U1") (pin "4") (pinfunction "PC15_4") (pintype "bidirectional"))
    )
    (net (code "84") (name "unconnected-(U1G-PC0-Pad8)") (class "Default")
      (node (ref "U1") (pin "8") (pinfunction "PC0_8") (pintype "bidirectional"))
    )
    (net (code "85") (name "unconnected-(U1G-PC3-Pad11)") (class "Default")
      (node (ref "U1") (pin "11") (pinfunction "PC3_11") (pintype "bidirectional"))
    )
    (net (code "86") (name "unconnected-(U1G-PC5-Pad25)") (class "Default")
      (node (ref "U1") (pin "25") (pinfunction "PC5_25") (pintype "bidirectional"))
    )
    (net (code "87") (name "unconnected-(U1H-PD2-Pad54)") (class "Default")
      (node (ref "U1") (pin "54") (pinfunction "PD2_54") (pintype "bidirectional"))
    )
  )
)
